# SPI_Module.net
KiCad netlist of a schematic drawn in Altium Designer
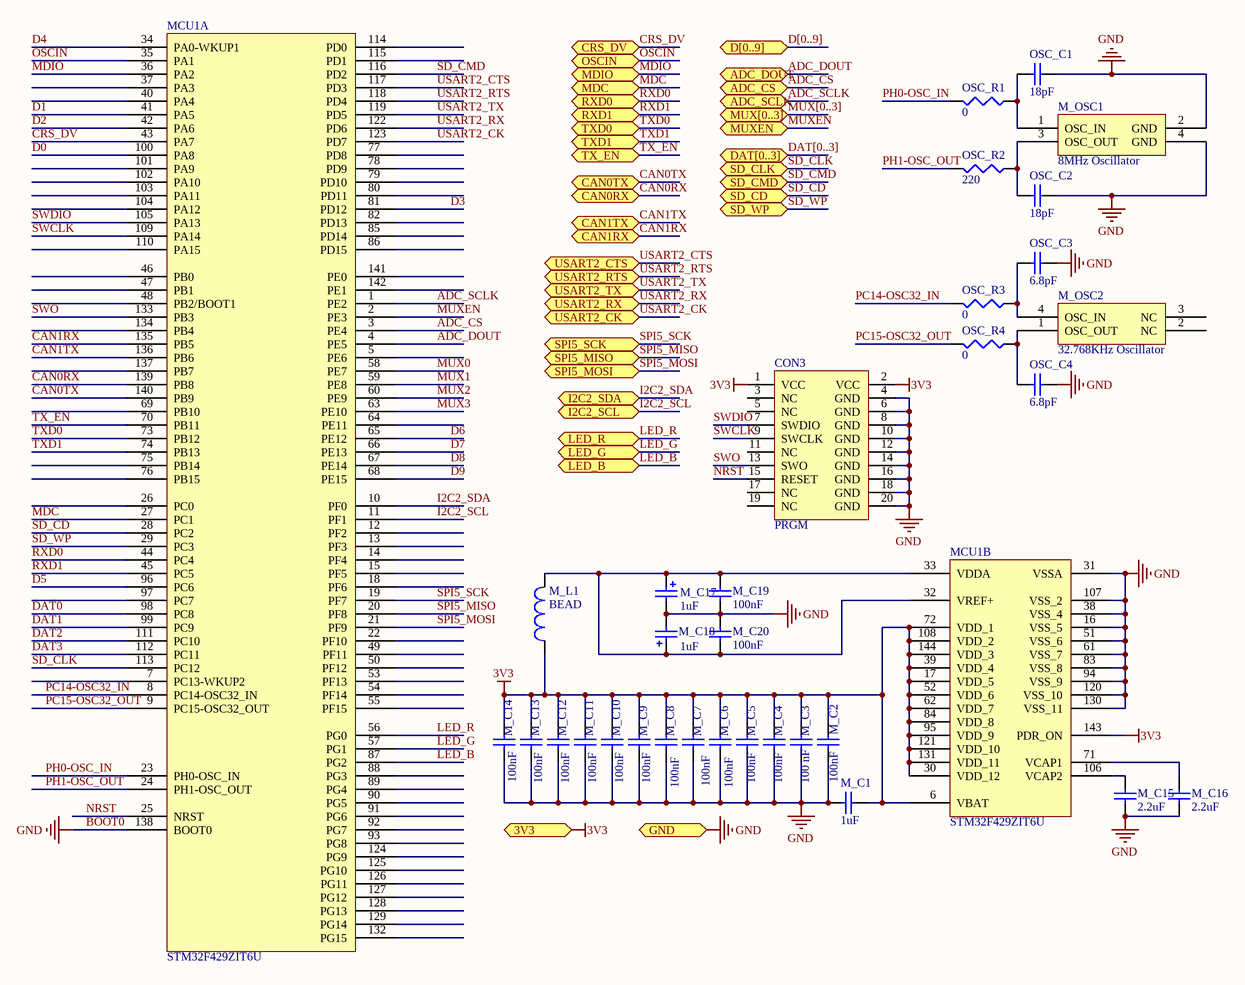
[diagram p0: SPI_Module.SchDoc]

(export (version "E")
  (design (tool "Eeschema 10.0.6"))
  (components
    (comp (ref "CON3")
      (value "PRGM")
      (footprint "JTAG/SWO-20PIN")
      (libsource (lib "Components") (part "JTAG/SWO-20PIN"))
    )
    (comp (ref "MCU1")
      (value "STM32F429ZIT6U")
      (footprint "LQPF144")
      (libsource (lib "Components") (part "STM32F429ZIT6U"))
    )
    (comp (ref "M_C1")
      (value "1uF")
      (footprint "SMD0603")
      (description "Ceramic Chip Capacitor")
      (fields (field (name "Comment") "Cap"))
      (libsource (lib "Components") (part "Capacitor Ceramic"))
    )
    (comp (ref "M_C2")
      (value "100nF")
      (footprint "SMD0603")
      (description "Ceramic Chip Capacitor")
      (fields (field (name "Comment") "Cap"))
      (libsource (lib "Components") (part "Capacitor Ceramic"))
    )
    (comp (ref "M_C3")
      (value "100 nF")
      (footprint "SMD0603")
      (description "Ceramic Chip Capacitor")
      (fields (field (name "Comment") "Cap"))
      (libsource (lib "Components") (part "Capacitor Ceramic"))
    )
    (comp (ref "M_C4")
      (value "100nF")
      (footprint "SMD0603")
      (description "Ceramic Chip Capacitor")
      (fields (field (name "Comment") "Cap"))
      (libsource (lib "Components") (part "Capacitor Ceramic"))
    )
    (comp (ref "M_C5")
      (value "100nF")
      (footprint "SMD0603")
      (description "Ceramic Chip Capacitor")
      (fields (field (name "Comment") "Cap"))
      (libsource (lib "Components") (part "Capacitor Ceramic"))
    )
    (comp (ref "M_C6")
      (value "100nF")
      (footprint "SMD0603")
      (description "Ceramic Chip Capacitor")
      (fields (field (name "Comment") "Cap"))
      (libsource (lib "Components") (part "Capacitor Ceramic"))
    )
    (comp (ref "M_C7")
      (value "100nF")
      (footprint "SMD0603")
      (description "Ceramic Chip Capacitor")
      (fields (field (name "Comment") "Cap"))
      (libsource (lib "Components") (part "Capacitor Ceramic"))
    )
    (comp (ref "M_C8")
      (value "100nF")
      (footprint "SMD0603")
      (description "Ceramic Chip Capacitor")
      (fields (field (name "Comment") "Cap"))
      (libsource (lib "Components") (part "Capacitor Ceramic"))
    )
    (comp (ref "M_C9")
      (value "100nF")
      (footprint "SMD0603")
      (description "Ceramic Chip Capacitor")
      (fields (field (name "Comment") "Cap"))
      (libsource (lib "Components") (part "Capacitor Ceramic"))
    )
    (comp (ref "M_C10")
      (value "100nF")
      (footprint "SMD0603")
      (description "Ceramic Chip Capacitor")
      (fields (field (name "Comment") "Cap"))
      (libsource (lib "Components") (part "Capacitor Ceramic"))
    )
    (comp (ref "M_C11")
      (value "100nF")
      (footprint "SMD0603")
      (description "Ceramic Chip Capacitor")
      (fields (field (name "Comment") "Cap"))
      (libsource (lib "Components") (part "Capacitor Ceramic"))
    )
    (comp (ref "M_C12")
      (value "100nF")
      (footprint "SMD0603")
      (description "Ceramic Chip Capacitor")
      (fields (field (name "Comment") "Cap"))
      (libsource (lib "Components") (part "Capacitor Ceramic"))
    )
    (comp (ref "M_C13")
      (value "100nF")
      (footprint "SMD0603")
      (description "Ceramic Chip Capacitor")
      (fields (field (name "Comment") "Cap"))
      (libsource (lib "Components") (part "Capacitor Ceramic"))
    )
    (comp (ref "M_C14")
      (value "100nF")
      (footprint "SMD0603")
      (description "Ceramic Chip Capacitor")
      (fields (field (name "Comment") "Cap"))
      (libsource (lib "Components") (part "Capacitor Ceramic"))
    )
    (comp (ref "M_C15")
      (value "2.2uF")
      (footprint "SMD1206")
      (description "Ceramic Chip Capacitor")
      (fields (field (name "Comment") "Cap"))
      (libsource (lib "Components") (part "Capacitor Ceramic"))
    )
    (comp (ref "M_C16")
      (value "2.2uF")
      (footprint "SMD1206")
      (description "Ceramic Chip Capacitor")
      (fields (field (name "Comment") "Cap"))
      (libsource (lib "Components") (part "Capacitor Ceramic"))
    )
    (comp (ref "M_C17")
      (value "1uF")
      (footprint "SMD1206 Polarized")
      (description "Polarized Capacitor (Surface Mount)")
      (fields (field (name "Comment") "Cap"))
      (libsource (lib "Components") (part "Capacitor Polarized"))
    )
    (comp (ref "M_C18")
      (value "1uF")
      (footprint "SMD1206 Polarized")
      (description "Polarized Capacitor (Surface Mount)")
      (fields (field (name "Comment") "Cap"))
      (libsource (lib "Components") (part "Capacitor Polarized"))
    )
    (comp (ref "M_C19")
      (value "100nF")
      (footprint "SMD0603")
      (description "Ceramic Chip Capacitor")
      (fields (field (name "Comment") "Cap"))
      (libsource (lib "Components") (part "Capacitor Ceramic"))
    )
    (comp (ref "M_C20")
      (value "100nF")
      (footprint "SMD0603")
      (description "Ceramic Chip Capacitor")
      (fields (field (name "Comment") "Cap"))
      (libsource (lib "Components") (part "Capacitor Ceramic"))
    )
    (comp (ref "M_L1")
      (value "BEAD")
      (footprint "SMD0603")
      (description "Ferrite Bead")
      (fields (field (name "PART") "BK1608HS601-TV"))
      (libsource (lib "Components") (part "Chip Ferrite Bead"))
    )
    (comp (ref "M_OSC1")
      (value "8MHz Oscillator")
      (footprint "ABMM2-OSC")
      (libsource (lib "Components") (part "ABMM2-8.000MHZ-E2-T"))
    )
    (comp (ref "M_OSC2")
      (value "32.768KHz Oscillator")
      (footprint "MC-306-OSC")
      (description "32.7680kHz Oscillator")
      (libsource (lib "Components") (part "MC-306 32.768K-E3"))
    )
    (comp (ref "OSC_C1")
      (value "18pF")
      (footprint "SMD0603")
      (description "Ceramic Chip Capacitor")
      (fields (field (name "Comment") "Cap"))
      (libsource (lib "Components") (part "Capacitor Ceramic"))
    )
    (comp (ref "OSC_C2")
      (value "18pF")
      (footprint "SMD0603")
      (description "Ceramic Chip Capacitor")
      (fields (field (name "Comment") "Cap"))
      (libsource (lib "Components") (part "Capacitor Ceramic"))
    )
    (comp (ref "OSC_C3")
      (value "6.8pF")
      (footprint "SMD0603")
      (description "Ceramic Chip Capacitor")
      (fields (field (name "Comment") "Cap"))
      (libsource (lib "Components") (part "Capacitor Ceramic"))
    )
    (comp (ref "OSC_C4")
      (value "6.8pF")
      (footprint "SMD0603")
      (description "Ceramic Chip Capacitor")
      (fields (field (name "Comment") "Cap"))
      (libsource (lib "Components") (part "Capacitor Ceramic"))
    )
    (comp (ref "OSC_R1")
      (value "0")
      (footprint "SMD0603")
      (description "Resistor")
      (fields (field (name "Comment") "Res"))
      (libsource (lib "Components") (part "Resistor"))
    )
    (comp (ref "OSC_R2")
      (value "220")
      (footprint "SMD0603")
      (description "Resistor")
      (fields (field (name "Comment") "Res"))
      (libsource (lib "Components") (part "Resistor"))
    )
    (comp (ref "OSC_R3")
      (value "0")
      (footprint "SMD0603")
      (description "Resistor")
      (fields (field (name "Comment") "Res"))
      (libsource (lib "Components") (part "Resistor"))
    )
    (comp (ref "OSC_R4")
      (value "0")
      (footprint "SMD0603")
      (description "Resistor")
      (fields (field (name "Comment") "Res"))
      (libsource (lib "Components") (part "Resistor"))
    )
  )
  (nets
    (net (code "1") (name "/ADC_CS") (class "Default")
      (node (ref "MCU1") (pin "3") (pinfunction "PE4_3") (pintype "passive"))
    )
    (net (code "2") (name "/ADC_DOUT") (class "Default")
      (node (ref "MCU1") (pin "4") (pinfunction "PE5_4") (pintype "passive"))
    )
    (net (code "3") (name "/ADC_SCLK") (class "Default")
      (node (ref "MCU1") (pin "1") (pinfunction "PE2_1") (pintype "passive"))
    )
    (net (code "4") (name "/CAN0RX") (class "Default")
      (node (ref "MCU1") (pin "139") (pinfunction "PB8_139") (pintype "passive"))
    )
    (net (code "5") (name "/CAN0TX") (class "Default")
      (node (ref "MCU1") (pin "140") (pinfunction "PB9_140") (pintype "passive"))
    )
    (net (code "6") (name "/CAN1RX") (class "Default")
      (node (ref "MCU1") (pin "135") (pinfunction "PB5_135") (pintype "passive"))
    )
    (net (code "7") (name "/CAN1TX") (class "Default")
      (node (ref "MCU1") (pin "136") (pinfunction "PB6_136") (pintype "passive"))
    )
    (net (code "8") (name "/CRS_DV") (class "Default")
      (node (ref "MCU1") (pin "43") (pinfunction "PA7_43") (pintype "passive"))
    )
    (net (code "9") (name "/D0") (class "Default")
      (node (ref "MCU1") (pin "100") (pinfunction "PA8_100") (pintype "passive"))
    )
    (net (code "10") (name "/D1") (class "Default")
      (node (ref "MCU1") (pin "41") (pinfunction "PA5_41") (pintype "passive"))
    )
    (net (code "11") (name "/D2") (class "Default")
      (node (ref "MCU1") (pin "42") (pinfunction "PA6_42") (pintype "passive"))
    )
    (net (code "12") (name "/D3") (class "Default")
      (node (ref "MCU1") (pin "81") (pinfunction "PD12_81") (pintype "passive"))
    )
    (net (code "13") (name "/D4") (class "Default")
      (node (ref "MCU1") (pin "34") (pinfunction "PA0-WKUP1_34") (pintype "passive"))
    )
    (net (code "14") (name "/D5") (class "Default")
      (node (ref "MCU1") (pin "96") (pinfunction "PC6_96") (pintype "passive"))
    )
    (net (code "15") (name "/D6") (class "Default")
      (node (ref "MCU1") (pin "65") (pinfunction "PE12_65") (pintype "passive"))
    )
    (net (code "16") (name "/D7") (class "Default")
      (node (ref "MCU1") (pin "66") (pinfunction "PE13_66") (pintype "passive"))
    )
    (net (code "17") (name "/D8") (class "Default")
      (node (ref "MCU1") (pin "67") (pinfunction "PE14_67") (pintype "passive"))
    )
    (net (code "18") (name "/D9") (class "Default")
      (node (ref "MCU1") (pin "68") (pinfunction "PE15_68") (pintype "passive"))
    )
    (net (code "19") (name "/DAT0") (class "Default")
      (node (ref "MCU1") (pin "98") (pinfunction "PC8_98") (pintype "passive"))
    )
    (net (code "20") (name "/DAT1") (class "Default")
      (node (ref "MCU1") (pin "99") (pinfunction "PC9_99") (pintype "passive"))
    )
    (net (code "21") (name "/DAT2") (class "Default")
      (node (ref "MCU1") (pin "111") (pinfunction "PC10_111") (pintype "passive"))
    )
    (net (code "22") (name "/DAT3") (class "Default")
      (node (ref "MCU1") (pin "112") (pinfunction "PC11_112") (pintype "passive"))
    )
    (net (code "25") (name "/I2C2_SCL") (class "Default")
      (node (ref "MCU1") (pin "11") (pinfunction "PF1_11") (pintype "passive"))
    )
    (net (code "26") (name "/I2C2_SDA") (class "Default")
      (node (ref "MCU1") (pin "10") (pinfunction "PF0_10") (pintype "passive"))
    )
    (net (code "27") (name "/LED_B") (class "Default")
      (node (ref "MCU1") (pin "87") (pinfunction "PG2_87") (pintype "passive"))
    )
    (net (code "28") (name "/LED_G") (class "Default")
      (node (ref "MCU1") (pin "57") (pinfunction "PG1_57") (pintype "passive"))
    )
    (net (code "29") (name "/LED_R") (class "Default")
      (node (ref "MCU1") (pin "56") (pinfunction "PG0_56") (pintype "passive"))
    )
    (net (code "30") (name "/MDC") (class "Default")
      (node (ref "MCU1") (pin "27") (pinfunction "PC1_27") (pintype "passive"))
    )
    (net (code "31") (name "/MDIO") (class "Default")
      (node (ref "MCU1") (pin "36") (pinfunction "PA2_36") (pintype "passive"))
    )
    (net (code "32") (name "/MUX0") (class "Default")
      (node (ref "MCU1") (pin "58") (pinfunction "PE7_58") (pintype "passive"))
    )
    (net (code "33") (name "/MUX1") (class "Default")
      (node (ref "MCU1") (pin "59") (pinfunction "PE8_59") (pintype "passive"))
    )
    (net (code "34") (name "/MUX2") (class "Default")
      (node (ref "MCU1") (pin "60") (pinfunction "PE9_60") (pintype "passive"))
    )
    (net (code "35") (name "/MUX3") (class "Default")
      (node (ref "MCU1") (pin "63") (pinfunction "PE10_63") (pintype "passive"))
    )
    (net (code "36") (name "/MUXEN") (class "Default")
      (node (ref "MCU1") (pin "2") (pinfunction "PE3_2") (pintype "passive"))
    )
    (net (code "38") (name "/NRST") (class "Default")
      (node (ref "CON3") (pin "15") (pinfunction "RESET_15") (pintype "passive"))
      (node (ref "MCU1") (pin "25") (pinfunction "NRST_25") (pintype "passive"))
    )
    (net (code "39") (name "/OSCIN") (class "Default")
      (node (ref "MCU1") (pin "35") (pinfunction "PA1_35") (pintype "passive"))
    )
    (net (code "40") (name "/PC14-OSC32_IN") (class "Default")
      (node (ref "MCU1") (pin "8") (pinfunction "PC14-OSC32_IN_8") (pintype "passive"))
      (node (ref "OSC_R3") (pin "2") (pinfunction "2_2") (pintype "passive"))
    )
    (net (code "41") (name "/PC15-OSC32_OUT") (class "Default")
      (node (ref "MCU1") (pin "9") (pinfunction "PC15-OSC32_OUT_9") (pintype "passive"))
      (node (ref "OSC_R4") (pin "2") (pinfunction "2_2") (pintype "passive"))
    )
    (net (code "42") (name "/PH0-OSC_IN") (class "Default")
      (node (ref "MCU1") (pin "23") (pinfunction "PH0-OSC_IN_23") (pintype "passive"))
      (node (ref "OSC_R1") (pin "2") (pinfunction "2_2") (pintype "passive"))
    )
    (net (code "43") (name "/PH1-OSC_OUT") (class "Default")
      (node (ref "MCU1") (pin "24") (pinfunction "PH1-OSC_OUT_24") (pintype "passive"))
      (node (ref "OSC_R2") (pin "2") (pinfunction "2_2") (pintype "passive"))
    )
    (net (code "44") (name "/RXD0") (class "Default")
      (node (ref "MCU1") (pin "44") (pinfunction "PC4_44") (pintype "passive"))
    )
    (net (code "45") (name "/RXD1") (class "Default")
      (node (ref "MCU1") (pin "45") (pinfunction "PC5_45") (pintype "passive"))
    )
    (net (code "46") (name "/SD_CD") (class "Default")
      (node (ref "MCU1") (pin "28") (pinfunction "PC2_28") (pintype "passive"))
    )
    (net (code "47") (name "/SD_CLK") (class "Default")
      (node (ref "MCU1") (pin "113") (pinfunction "PC12_113") (pintype "passive"))
    )
    (net (code "48") (name "/SD_CMD") (class "Default")
      (node (ref "MCU1") (pin "116") (pinfunction "PD2_116") (pintype "passive"))
    )
    (net (code "49") (name "/SD_WP") (class "Default")
      (node (ref "MCU1") (pin "29") (pinfunction "PC3_29") (pintype "passive"))
    )
    (net (code "50") (name "/SPI5_MISO") (class "Default")
      (node (ref "MCU1") (pin "20") (pinfunction "PF8_20") (pintype "passive"))
    )
    (net (code "51") (name "/SPI5_MOSI") (class "Default")
      (node (ref "MCU1") (pin "21") (pinfunction "PF9_21") (pintype "passive"))
    )
    (net (code "52") (name "/SPI5_SCK") (class "Default")
      (node (ref "MCU1") (pin "19") (pinfunction "PF7_19") (pintype "passive"))
    )
    (net (code "53") (name "/SWCLK") (class "Default")
      (node (ref "CON3") (pin "9") (pinfunction "SWCLK_9") (pintype "passive"))
      (node (ref "MCU1") (pin "109") (pinfunction "PA14_109") (pintype "passive"))
    )
    (net (code "54") (name "/SWDIO") (class "Default")
      (node (ref "CON3") (pin "7") (pinfunction "SWDIO_7") (pintype "passive"))
      (node (ref "MCU1") (pin "105") (pinfunction "PA13_105") (pintype "passive"))
    )
    (net (code "55") (name "/SWO") (class "Default")
      (node (ref "CON3") (pin "13") (pinfunction "SWO_13") (pintype "passive"))
      (node (ref "MCU1") (pin "133") (pinfunction "PB3_133") (pintype "passive"))
    )
    (net (code "56") (name "/TXD0") (class "Default")
      (node (ref "MCU1") (pin "73") (pinfunction "PB12_73") (pintype "passive"))
    )
    (net (code "57") (name "/TXD1") (class "Default")
      (node (ref "MCU1") (pin "74") (pinfunction "PB13_74") (pintype "passive"))
    )
    (net (code "58") (name "/TX_EN") (class "Default")
      (node (ref "MCU1") (pin "70") (pinfunction "PB11_70") (pintype "passive"))
    )
    (net (code "59") (name "/USART2_CK") (class "Default")
      (node (ref "MCU1") (pin "123") (pinfunction "PD7_123") (pintype "passive"))
    )
    (net (code "60") (name "/USART2_CTS") (class "Default")
      (node (ref "MCU1") (pin "117") (pinfunction "PD3_117") (pintype "passive"))
    )
    (net (code "61") (name "/USART2_RTS") (class "Default")
      (node (ref "MCU1") (pin "118") (pinfunction "PD4_118") (pintype "passive"))
    )
    (net (code "62") (name "/USART2_RX") (class "Default")
      (node (ref "MCU1") (pin "122") (pinfunction "PD6_122") (pintype "passive"))
    )
    (net (code "63") (name "/USART2_TX") (class "Default")
      (node (ref "MCU1") (pin "119") (pinfunction "PD5_119") (pintype "passive"))
    )
    (net (code "64") (name "3V3") (class "Default")
      (node (ref "CON3") (pin "1") (pinfunction "VCC_1") (pintype "passive"))
      (node (ref "CON3") (pin "2") (pinfunction "VCC_2") (pintype "passive"))
      (node (ref "MCU1") (pin "108") (pinfunction "VDD_2_108") (pintype "passive"))
      (node (ref "MCU1") (pin "121") (pinfunction "VDD_10_121") (pintype "passive"))
      (node (ref "MCU1") (pin "131") (pinfunction "VDD_11_131") (pintype "passive"))
      (node (ref "MCU1") (pin "143") (pinfunction "PDR_ON_143") (pintype "passive"))
      (node (ref "MCU1") (pin "144") (pinfunction "VDD_3_144") (pintype "passive"))
      (node (ref "MCU1") (pin "17") (pinfunction "VDD_5_17") (pintype "passive"))
      (node (ref "MCU1") (pin "30") (pinfunction "VDD_12_30") (pintype "passive"))
      (node (ref "MCU1") (pin "39") (pinfunction "VDD_4_39") (pintype "passive"))
      (node (ref "MCU1") (pin "52") (pinfunction "VDD_6_52") (pintype "passive"))
      (node (ref "MCU1") (pin "6") (pinfunction "VBAT_6") (pintype "passive"))
      (node (ref "MCU1") (pin "62") (pinfunction "VDD_7_62") (pintype "passive"))
      (node (ref "MCU1") (pin "72") (pinfunction "VDD_1_72") (pintype "passive"))
      (node (ref "MCU1") (pin "84") (pinfunction "VDD_8_84") (pintype "passive"))
      (node (ref "MCU1") (pin "95") (pinfunction "VDD_9_95") (pintype "passive"))
      (node (ref "M_C1") (pin "1") (pinfunction "1_1") (pintype "passive"))
      (node (ref "M_C10") (pin "2") (pinfunction "2_2") (pintype "passive"))
      (node (ref "M_C11") (pin "2") (pinfunction "2_2") (pintype "passive"))
      (node (ref "M_C12") (pin "2") (pinfunction "2_2") (pintype "passive"))
      (node (ref "M_C13") (pin "2") (pinfunction "2_2") (pintype "passive"))
      (node (ref "M_C14") (pin "2") (pinfunction "2_2") (pintype "passive"))
      (node (ref "M_C2") (pin "1") (pinfunction "1_1") (pintype "passive"))
      (node (ref "M_C3") (pin "2") (pinfunction "2_2") (pintype "passive"))
      (node (ref "M_C4") (pin "2") (pinfunction "2_2") (pintype "passive"))
      (node (ref "M_C5") (pin "2") (pinfunction "2_2") (pintype "passive"))
      (node (ref "M_C6") (pin "2") (pinfunction "2_2") (pintype "passive"))
      (node (ref "M_C7") (pin "2") (pinfunction "2_2") (pintype "passive"))
      (node (ref "M_C8") (pin "2") (pinfunction "2_2") (pintype "passive"))
      (node (ref "M_C9") (pin "2") (pinfunction "2_2") (pintype "passive"))
      (node (ref "M_L1") (pin "1") (pintype "passive"))
    )
    (net (code "65") (name "GND") (class "Default")
      (node (ref "CON3") (pin "10") (pinfunction "GND_10") (pintype "passive"))
      (node (ref "CON3") (pin "12") (pinfunction "GND_12") (pintype "passive"))
      (node (ref "CON3") (pin "14") (pinfunction "GND_14") (pintype "passive"))
      (node (ref "CON3") (pin "16") (pinfunction "GND_16") (pintype "passive"))
      (node (ref "CON3") (pin "18") (pinfunction "GND_18") (pintype "passive"))
      (node (ref "CON3") (pin "20") (pinfunction "GND_20") (pintype "passive"))
      (node (ref "CON3") (pin "4") (pinfunction "GND_4") (pintype "passive"))
      (node (ref "CON3") (pin "6") (pinfunction "GND_6") (pintype "passive"))
      (node (ref "CON3") (pin "8") (pinfunction "GND_8") (pintype "passive"))
      (node (ref "MCU1") (pin "107") (pinfunction "VSS_2_107") (pintype "passive"))
      (node (ref "MCU1") (pin "120") (pinfunction "VSS_10_120") (pintype "passive"))
      (node (ref "MCU1") (pin "130") (pinfunction "VSS_11_130") (pintype "passive"))
      (node (ref "MCU1") (pin "138") (pinfunction "BOOT0_138") (pintype "passive"))
      (node (ref "MCU1") (pin "16") (pinfunction "VSS_5_16") (pintype "passive"))
      (node (ref "MCU1") (pin "31") (pinfunction "VSSA_31") (pintype "passive"))
      (node (ref "MCU1") (pin "38") (pinfunction "VSS_4_38") (pintype "passive"))
      (node (ref "MCU1") (pin "51") (pinfunction "VSS_6_51") (pintype "passive"))
      (node (ref "MCU1") (pin "61") (pinfunction "VSS_7_61") (pintype "passive"))
      (node (ref "MCU1") (pin "83") (pinfunction "VSS_8_83") (pintype "passive"))
      (node (ref "MCU1") (pin "94") (pinfunction "VSS_9_94") (pintype "passive"))
      (node (ref "M_C1") (pin "2") (pinfunction "2_2") (pintype "passive"))
      (node (ref "M_C10") (pin "1") (pinfunction "1_1") (pintype "passive"))
      (node (ref "M_C11") (pin "1") (pinfunction "1_1") (pintype "passive"))
      (node (ref "M_C12") (pin "1") (pinfunction "1_1") (pintype "passive"))
      (node (ref "M_C13") (pin "1") (pinfunction "1_1") (pintype "passive"))
      (node (ref "M_C14") (pin "1") (pinfunction "1_1") (pintype "passive"))
      (node (ref "M_C15") (pin "1") (pinfunction "1_1") (pintype "passive"))
      (node (ref "M_C16") (pin "1") (pinfunction "1_1") (pintype "passive"))
      (node (ref "M_C17") (pin "2") (pinfunction "2_2") (pintype "passive"))
      (node (ref "M_C18") (pin "2") (pinfunction "2_2") (pintype "passive"))
      (node (ref "M_C19") (pin "1") (pinfunction "1_1") (pintype "passive"))
      (node (ref "M_C2") (pin "2") (pinfunction "2_2") (pintype "passive"))
      (node (ref "M_C20") (pin "2") (pinfunction "2_2") (pintype "passive"))
      (node (ref "M_C3") (pin "1") (pinfunction "1_1") (pintype "passive"))
      (node (ref "M_C4") (pin "1") (pinfunction "1_1") (pintype "passive"))
      (node (ref "M_C5") (pin "1") (pinfunction "1_1") (pintype "passive"))
      (node (ref "M_C6") (pin "1") (pinfunction "1_1") (pintype "passive"))
      (node (ref "M_C7") (pin "1") (pinfunction "1_1") (pintype "passive"))
      (node (ref "M_C8") (pin "1") (pinfunction "1_1") (pintype "passive"))
      (node (ref "M_C9") (pin "1") (pinfunction "1_1") (pintype "passive"))
      (node (ref "M_OSC1") (pin "2") (pinfunction "GND_2") (pintype "passive"))
      (node (ref "M_OSC1") (pin "4") (pinfunction "GND_4") (pintype "passive"))
      (node (ref "OSC_C1") (pin "1") (pinfunction "1_1") (pintype "passive"))
      (node (ref "OSC_C2") (pin "1") (pinfunction "1_1") (pintype "passive"))
      (node (ref "OSC_C3") (pin "1") (pinfunction "1_1") (pintype "passive"))
      (node (ref "OSC_C4") (pin "1") (pinfunction "1_1") (pintype "passive"))
    )
    (net (code "66") (name "Net-(MCU1B-VCAP1)") (class "Default")
      (node (ref "MCU1") (pin "71") (pinfunction "VCAP1_71") (pintype "passive"))
      (node (ref "M_C16") (pin "2") (pinfunction "2_2") (pintype "passive"))
    )
    (net (code "67") (name "Net-(MCU1B-VCAP2)") (class "Default")
      (node (ref "MCU1") (pin "106") (pinfunction "VCAP2_106") (pintype "passive"))
      (node (ref "M_C15") (pin "2") (pinfunction "2_2") (pintype "passive"))
    )
    (net (code "68") (name "Net-(MCU1B-VDDA)") (class "Default")
      (node (ref "MCU1") (pin "32") (pinfunction "VREF+_32") (pintype "passive"))
      (node (ref "MCU1") (pin "33") (pinfunction "VDDA_33") (pintype "passive"))
      (node (ref "M_C17") (pin "1") (pinfunction "1_1") (pintype "passive"))
      (node (ref "M_C18") (pin "1") (pinfunction "1_1") (pintype "passive"))
      (node (ref "M_C19") (pin "2") (pinfunction "2_2") (pintype "passive"))
      (node (ref "M_C20") (pin "1") (pinfunction "1_1") (pintype "passive"))
      (node (ref "M_L1") (pin "2") (pintype "passive"))
    )
    (net (code "69") (name "Net-(M_OSC1-OSC_IN)") (class "Default")
      (node (ref "M_OSC1") (pin "1") (pinfunction "OSC_IN_1") (pintype "passive"))
      (node (ref "OSC_C1") (pin "2") (pinfunction "2_2") (pintype "passive"))
      (node (ref "OSC_R1") (pin "1") (pinfunction "1_1") (pintype "passive"))
    )
    (net (code "70") (name "Net-(M_OSC1-OSC_OUT)") (class "Default")
      (node (ref "M_OSC1") (pin "3") (pinfunction "OSC_OUT_3") (pintype "passive"))
      (node (ref "OSC_C2") (pin "2") (pinfunction "2_2") (pintype "passive"))
      (node (ref "OSC_R2") (pin "1") (pinfunction "1_1") (pintype "passive"))
    )
    (net (code "71") (name "Net-(M_OSC2-OSC_IN)") (class "Default")
      (node (ref "M_OSC2") (pin "4") (pinfunction "OSC_IN_4") (pintype "passive"))
      (node (ref "OSC_C3") (pin "2") (pinfunction "2_2") (pintype "passive"))
      (node (ref "OSC_R3") (pin "1") (pinfunction "1_1") (pintype "passive"))
    )
    (net (code "72") (name "Net-(M_OSC2-OSC_OUT)") (class "Default")
      (node (ref "M_OSC2") (pin "1") (pinfunction "OSC_OUT_1") (pintype "passive"))
      (node (ref "OSC_C4") (pin "2") (pinfunction "2_2") (pintype "passive"))
      (node (ref "OSC_R4") (pin "1") (pinfunction "1_1") (pintype "passive"))
    )
    (net (code "73") (name "unconnected-(CON3-NC-Pad3)") (class "Default")
      (node (ref "CON3") (pin "3") (pinfunction "NC_3") (pintype "passive"))
    )
    (net (code "74") (name "unconnected-(CON3-NC-Pad5)") (class "Default")
      (node (ref "CON3") (pin "5") (pinfunction "NC_5") (pintype "passive"))
    )
    (net (code "75") (name "unconnected-(CON3-NC-Pad11)") (class "Default")
      (node (ref "CON3") (pin "11") (pinfunction "NC_11") (pintype "passive"))
    )
    (net (code "76") (name "unconnected-(CON3-NC-Pad17)") (class "Default")
      (node (ref "CON3") (pin "17") (pinfunction "NC_17") (pintype "passive"))
    )
    (net (code "77") (name "unconnected-(CON3-NC-Pad19)") (class "Default")
      (node (ref "CON3") (pin "19") (pinfunction "NC_19") (pintype "passive"))
    )
    (net (code "78") (name "unconnected-(MCU1A-PA3-Pad37)") (class "Default")
      (node (ref "MCU1") (pin "37") (pinfunction "PA3_37") (pintype "passive"))
    )
    (net (code "79") (name "unconnected-(MCU1A-PA4-Pad40)") (class "Default")
      (node (ref "MCU1") (pin "40") (pinfunction "PA4_40") (pintype "passive"))
    )
    (net (code "80") (name "unconnected-(MCU1A-PA9-Pad101)") (class "Default")
      (node (ref "MCU1") (pin "101") (pinfunction "PA9_101") (pintype "passive"))
    )
    (net (code "81") (name "unconnected-(MCU1A-PA10-Pad102)") (class "Default")
      (node (ref "MCU1") (pin "102") (pinfunction "PA10_102") (pintype "passive"))
    )
    (net (code "82") (name "unconnected-(MCU1A-PA11-Pad103)") (class "Default")
      (node (ref "MCU1") (pin "103") (pinfunction "PA11_103") (pintype "passive"))
    )
    (net (code "83") (name "unconnected-(MCU1A-PA12-Pad104)") (class "Default")
      (node (ref "MCU1") (pin "104") (pinfunction "PA12_104") (pintype "passive"))
    )
    (net (code "84") (name "unconnected-(MCU1A-PA15-Pad110)") (class "Default")
      (node (ref "MCU1") (pin "110") (pinfunction "PA15_110") (pintype "passive"))
    )
    (net (code "85") (name "unconnected-(MCU1A-PB0-Pad46)") (class "Default")
      (node (ref "MCU1") (pin "46") (pinfunction "PB0_46") (pintype "passive"))
    )
    (net (code "86") (name "unconnected-(MCU1A-PB1-Pad47)") (class "Default")
      (node (ref "MCU1") (pin "47") (pinfunction "PB1_47") (pintype "passive"))
    )
    (net (code "87") (name "unconnected-(MCU1A-PB2{slash}BOOT1-Pad48)") (class "Default")
      (node (ref "MCU1") (pin "48") (pinfunction "PB2/BOOT1_48") (pintype "passive"))
    )
    (net (code "88") (name "unconnected-(MCU1A-PB4-Pad134)") (class "Default")
      (node (ref "MCU1") (pin "134") (pinfunction "PB4_134") (pintype "passive"))
    )
    (net (code "89") (name "unconnected-(MCU1A-PB7-Pad137)") (class "Default")
      (node (ref "MCU1") (pin "137") (pinfunction "PB7_137") (pintype "passive"))
    )
    (net (code "90") (name "unconnected-(MCU1A-PB10-Pad69)") (class "Default")
      (node (ref "MCU1") (pin "69") (pinfunction "PB10_69") (pintype "passive"))
    )
    (net (code "91") (name "unconnected-(MCU1A-PB14-Pad75)") (class "Default")
      (node (ref "MCU1") (pin "75") (pinfunction "PB14_75") (pintype "passive"))
    )
    (net (code "92") (name "unconnected-(MCU1A-PB15-Pad76)") (class "Default")
      (node (ref "MCU1") (pin "76") (pinfunction "PB15_76") (pintype "passive"))
    )
    (net (code "93") (name "unconnected-(MCU1A-PC0-Pad26)") (class "Default")
      (node (ref "MCU1") (pin "26") (pinfunction "PC0_26") (pintype "passive"))
    )
    (net (code "94") (name "unconnected-(MCU1A-PC7-Pad97)") (class "Default")
      (node (ref "MCU1") (pin "97") (pinfunction "PC7_97") (pintype "passive"))
    )
    (net (code "95") (name "unconnected-(MCU1A-PC13-WKUP2-Pad7)") (class "Default")
      (node (ref "MCU1") (pin "7") (pinfunction "PC13-WKUP2_7") (pintype "passive"))
    )
    (net (code "96") (name "unconnected-(MCU1A-PD0-Pad114)") (class "Default")
      (node (ref "MCU1") (pin "114") (pinfunction "PD0_114") (pintype "passive"))
    )
    (net (code "97") (name "unconnected-(MCU1A-PD1-Pad115)") (class "Default")
      (node (ref "MCU1") (pin "115") (pinfunction "PD1_115") (pintype "passive"))
    )
    (net (code "98") (name "unconnected-(MCU1A-PD8-Pad77)") (class "Default")
      (node (ref "MCU1") (pin "77") (pinfunction "PD8_77") (pintype "passive"))
    )
    (net (code "99") (name "unconnected-(MCU1A-PD9-Pad78)") (class "Default")
      (node (ref "MCU1") (pin "78") (pinfunction "PD9_78") (pintype "passive"))
    )
    (net (code "100") (name "unconnected-(MCU1A-PD10-Pad79)") (class "Default")
      (node (ref "MCU1") (pin "79") (pinfunction "PD10_79") (pintype "passive"))
    )
    (net (code "101") (name "unconnected-(MCU1A-PD11-Pad80)") (class "Default")
      (node (ref "MCU1") (pin "80") (pinfunction "PD11_80") (pintype "passive"))
    )
    (net (code "102") (name "unconnected-(MCU1A-PD13-Pad82)") (class "Default")
      (node (ref "MCU1") (pin "82") (pinfunction "PD13_82") (pintype "passive"))
    )
    (net (code "103") (name "unconnected-(MCU1A-PD14-Pad85)") (class "Default")
      (node (ref "MCU1") (pin "85") (pinfunction "PD14_85") (pintype "passive"))
    )
    (net (code "104") (name "unconnected-(MCU1A-PD15-Pad86)") (class "Default")
      (node (ref "MCU1") (pin "86") (pinfunction "PD15_86") (pintype "passive"))
    )
    (net (code "105") (name "unconnected-(MCU1A-PE0-Pad141)") (class "Default")
      (node (ref "MCU1") (pin "141") (pinfunction "PE0_141") (pintype "passive"))
    )
    (net (code "106") (name "unconnected-(MCU1A-PE1-Pad142)") (class "Default")
      (node (ref "MCU1") (pin "142") (pinfunction "PE1_142") (pintype "passive"))
    )
    (net (code "107") (name "unconnected-(MCU1A-PE6-Pad5)") (class "Default")
      (node (ref "MCU1") (pin "5") (pinfunction "PE6_5") (pintype "passive"))
    )
    (net (code "108") (name "unconnected-(MCU1A-PE11-Pad64)") (class "Default")
      (node (ref "MCU1") (pin "64") (pinfunction "PE11_64") (pintype "passive"))
    )
    (net (code "109") (name "unconnected-(MCU1A-PF2-Pad12)") (class "Default")
      (node (ref "MCU1") (pin "12") (pinfunction "PF2_12") (pintype "passive"))
    )
    (net (code "110") (name "unconnected-(MCU1A-PF3-Pad13)") (class "Default")
      (node (ref "MCU1") (pin "13") (pinfunction "PF3_13") (pintype "passive"))
    )
    (net (code "111") (name "unconnected-(MCU1A-PF4-Pad14)") (class "Default")
      (node (ref "MCU1") (pin "14") (pinfunction "PF4_14") (pintype "passive"))
    )
    (net (code "112") (name "unconnected-(MCU1A-PF5-Pad15)") (class "Default")
      (node (ref "MCU1") (pin "15") (pinfunction "PF5_15") (pintype "passive"))
    )
    (net (code "113") (name "unconnected-(MCU1A-PF6-Pad18)") (class "Default")
      (node (ref "MCU1") (pin "18") (pinfunction "PF6_18") (pintype "passive"))
    )
    (net (code "114") (name "unconnected-(MCU1A-PF10-Pad22)") (class "Default")
      (node (ref "MCU1") (pin "22") (pinfunction "PF10_22") (pintype "passive"))
    )
    (net (code "115") (name "unconnected-(MCU1A-PF11-Pad49)") (class "Default")
      (node (ref "MCU1") (pin "49") (pinfunction "PF11_49") (pintype "passive"))
    )
    (net (code "116") (name "unconnected-(MCU1A-PF12-Pad50)") (class "Default")
      (node (ref "MCU1") (pin "50") (pinfunction "PF12_50") (pintype "passive"))
    )
    (net (code "117") (name "unconnected-(MCU1A-PF13-Pad53)") (class "Default")
      (node (ref "MCU1") (pin "53") (pinfunction "PF13_53") (pintype "passive"))
    )
    (net (code "118") (name "unconnected-(MCU1A-PF14-Pad54)") (class "Default")
      (node (ref "MCU1") (pin "54") (pinfunction "PF14_54") (pintype "passive"))
    )
    (net (code "119") (name "unconnected-(MCU1A-PF15-Pad55)") (class "Default")
      (node (ref "MCU1") (pin "55") (pinfunction "PF15_55") (pintype "passive"))
    )
    (net (code "120") (name "unconnected-(MCU1A-PG3-Pad88)") (class "Default")
      (node (ref "MCU1") (pin "88") (pinfunction "PG3_88") (pintype "passive"))
    )
    (net (code "121") (name "unconnected-(MCU1A-PG4-Pad89)") (class "Default")
      (node (ref "MCU1") (pin "89") (pinfunction "PG4_89") (pintype "passive"))
    )
    (net (code "122") (name "unconnected-(MCU1A-PG5-Pad90)") (class "Default")
      (node (ref "MCU1") (pin "90") (pinfunction "PG5_90") (pintype "passive"))
    )
    (net (code "123") (name "unconnected-(MCU1A-PG6-Pad91)") (class "Default")
      (node (ref "MCU1") (pin "91") (pinfunction "PG6_91") (pintype "passive"))
    )
    (net (code "124") (name "unconnected-(MCU1A-PG7-Pad92)") (class "Default")
      (node (ref "MCU1") (pin "92") (pinfunction "PG7_92") (pintype "passive"))
    )
    (net (code "125") (name "unconnected-(MCU1A-PG8-Pad93)") (class "Default")
      (node (ref "MCU1") (pin "93") (pinfunction "PG8_93") (pintype "passive"))
    )
    (net (code "126") (name "unconnected-(MCU1A-PG9-Pad124)") (class "Default")
      (node (ref "MCU1") (pin "124") (pinfunction "PG9_124") (pintype "passive"))
    )
    (net (code "127") (name "unconnected-(MCU1A-PG10-Pad125)") (class "Default")
      (node (ref "MCU1") (pin "125") (pinfunction "PG10_125") (pintype "passive"))
    )
    (net (code "128") (name "unconnected-(MCU1A-PG11-Pad126)") (class "Default")
      (node (ref "MCU1") (pin "126") (pinfunction "PG11_126") (pintype "passive"))
    )
    (net (code "129") (name "unconnected-(MCU1A-PG12-Pad127)") (class "Default")
      (node (ref "MCU1") (pin "127") (pinfunction "PG12_127") (pintype "passive"))
    )
    (net (code "130") (name "unconnected-(MCU1A-PG13-Pad128)") (class "Default")
      (node (ref "MCU1") (pin "128") (pinfunction "PG13_128") (pintype "passive"))
    )
    (net (code "131") (name "unconnected-(MCU1A-PG14-Pad129)") (class "Default")
      (node (ref "MCU1") (pin "129") (pinfunction "PG14_129") (pintype "passive"))
    )
    (net (code "132") (name "unconnected-(MCU1A-PG15-Pad132)") (class "Default")
      (node (ref "MCU1") (pin "132") (pinfunction "PG15_132") (pintype "passive"))
    )
    (net (code "133") (name "unconnected-(M_OSC2-NC-Pad2)") (class "Default")
      (node (ref "M_OSC2") (pin "2") (pinfunction "NC_2") (pintype "passive"))
    )
    (net (code "134") (name "unconnected-(M_OSC2-NC-Pad3)") (class "Default")
      (node (ref "M_OSC2") (pin "3") (pinfunction "NC_3") (pintype "passive"))
    )
  )
)
